# Auxillary_Supply_UCC28740.net
KiCad netlist of a schematic drawn in Altium Designer
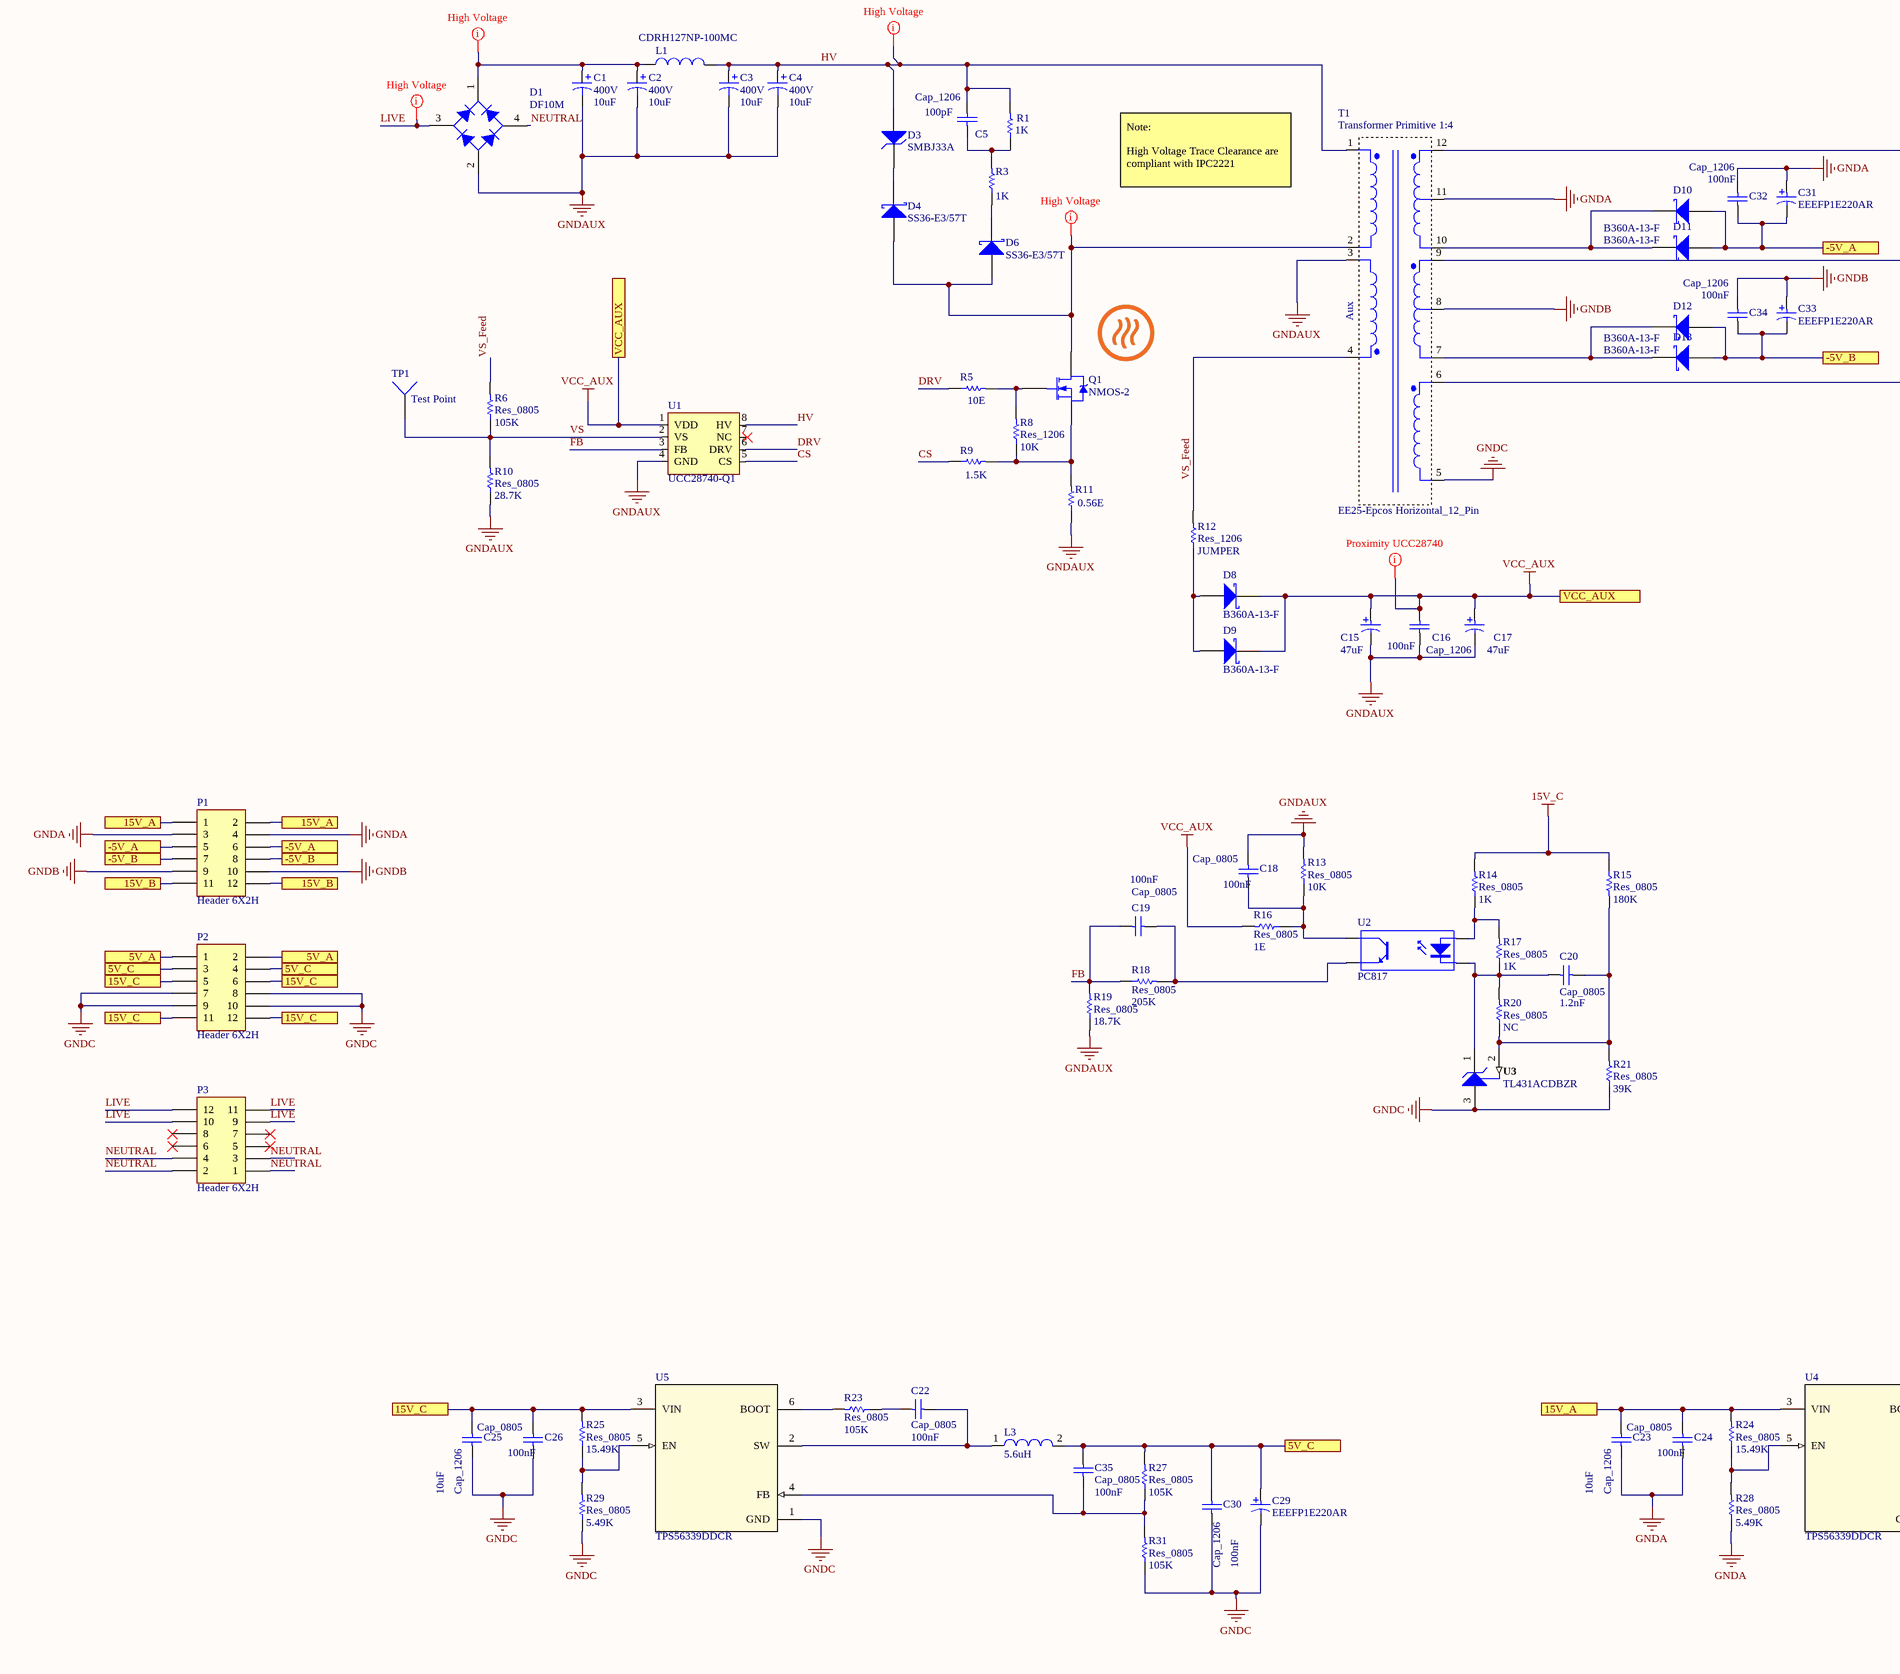
[diagram p0: Auxillary_Supply_UCC28740.SchDoc, left]
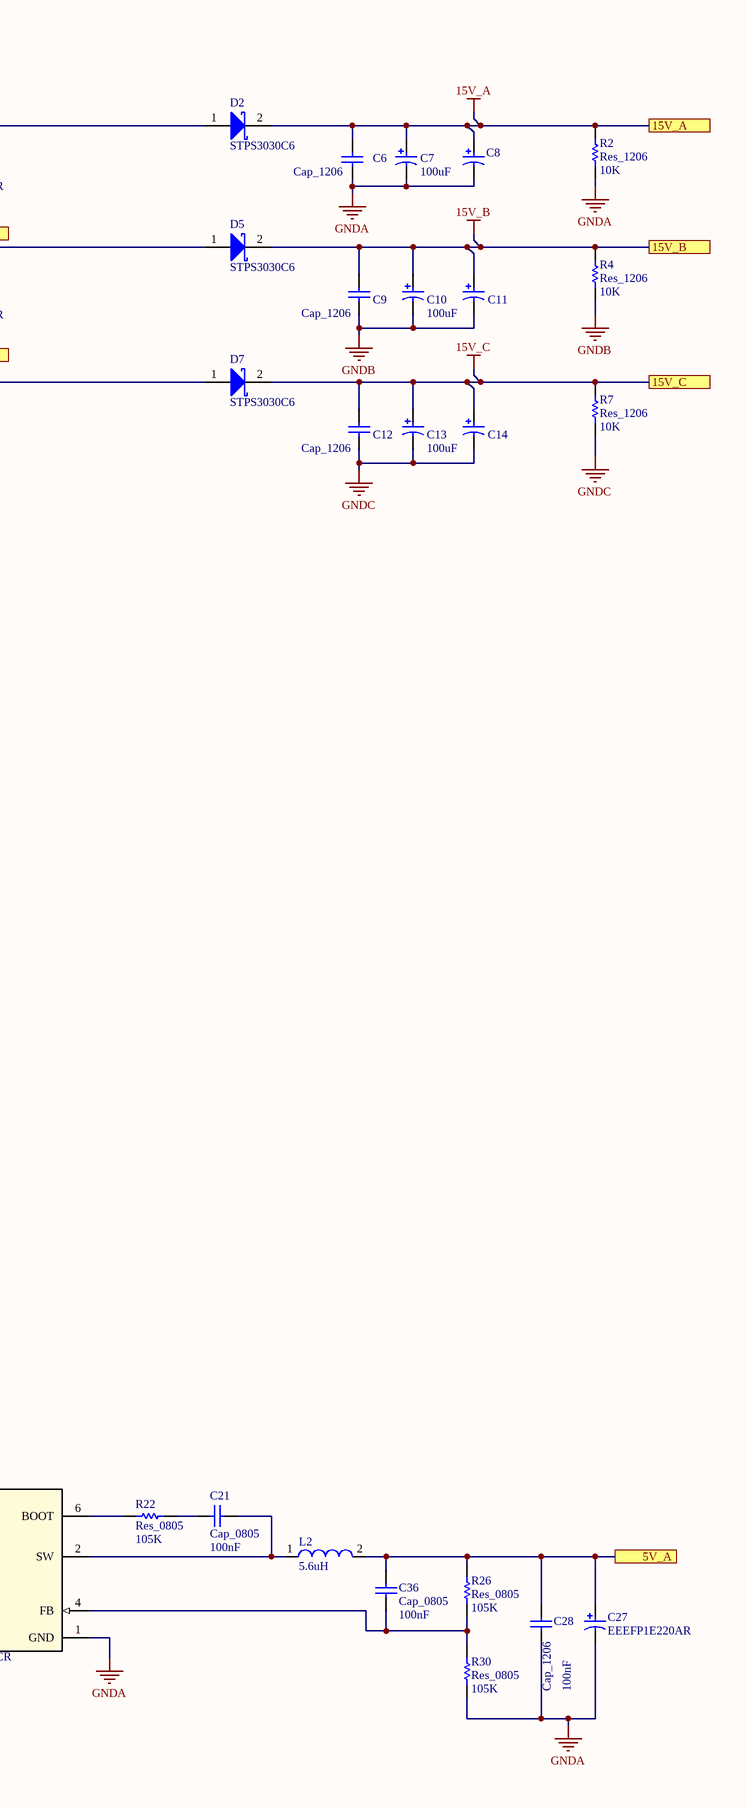
[diagram p1: Auxillary_Supply_UCC28740.SchDoc, right]

(export (version "E")
  (design (tool "Eeschema 10.0.6"))
  (components
    (comp (ref "C1")
      (value "400V")
      (footprint "10uF_400V")
      (description "Polarized Capacitor (Radial)")
      (fields (field (name "ALTIUM_VALUE") "10uF") (field (name "PUBLISHER") "Altium Limited"))
      (libsource (lib "Miscellaneous Devices") (part "Cap Pol1"))
    )
    (comp (ref "C2")
      (value "400V")
      (footprint "10uF_400V")
      (description "Polarized Capacitor (Radial)")
      (fields (field (name "ALTIUM_VALUE") "10uF") (field (name "PUBLISHER") "Altium Limited"))
      (libsource (lib "Miscellaneous Devices") (part "Cap Pol1"))
    )
    (comp (ref "C3")
      (value "400V")
      (footprint "10uF_400V")
      (description "Polarized Capacitor (Radial)")
      (fields (field (name "ALTIUM_VALUE") "10uF") (field (name "PUBLISHER") "Altium Limited"))
      (libsource (lib "Miscellaneous Devices") (part "Cap Pol1"))
    )
    (comp (ref "C4")
      (value "400V")
      (footprint "10uF_400V")
      (description "Polarized Capacitor (Radial)")
      (fields (field (name "ALTIUM_VALUE") "10uF") (field (name "PUBLISHER") "Altium Limited"))
      (libsource (lib "Miscellaneous Devices") (part "Cap Pol1"))
    )
    (comp (ref "C5")
      (value "Cap_1206")
      (footprint "Chip_CAP_1206")
      (description "Capacitor")
      (fields (field (name "ALTIUM_VALUE") "100pF") (field (name "PUBLISHER") "Altium Limited"))
      (libsource (lib "Miscellaneous Devices") (part "Cap"))
    )
    (comp (ref "C6")
      (value "Cap_1206")
      (footprint "Chip_CAP_1206")
      (description "Capacitor")
      (fields (field (name "PUBLISHER") "Altium Limited"))
      (libsource (lib "Miscellaneous Devices") (part "Cap"))
    )
    (comp (ref "C7")
      (value "100uF")
      (footprint "PNSC-FK-V-F_V")
      (fields (field (name "MANUFACTURER") "Panasonic"))
      (libsource (lib "Altium Content Vault") (part "CAP-P-2"))
    )
    (comp (ref "C8")
      (value "100uF")
      (footprint "PNSC-FK-V-F_V")
      (fields (field (name "MANUFACTURER") "Panasonic"))
      (libsource (lib "Altium Content Vault") (part "CAP-P-2"))
    )
    (comp (ref "C9")
      (value "Cap_1206")
      (footprint "Chip_CAP_1206")
      (description "Capacitor")
      (fields (field (name "PUBLISHER") "Altium Limited"))
      (libsource (lib "Miscellaneous Devices") (part "Cap"))
    )
    (comp (ref "C10")
      (value "100uF")
      (footprint "PNSC-FK-V-F_V")
      (fields (field (name "MANUFACTURER") "Panasonic"))
      (libsource (lib "Altium Content Vault") (part "CAP-P-2"))
    )
    (comp (ref "C11")
      (value "100uF")
      (footprint "PNSC-FK-V-F_V")
      (fields (field (name "MANUFACTURER") "Panasonic"))
      (libsource (lib "Altium Content Vault") (part "CAP-P-2"))
    )
    (comp (ref "C12")
      (value "Cap_1206")
      (footprint "Chip_CAP_1206")
      (description "Capacitor")
      (fields (field (name "PUBLISHER") "Altium Limited"))
      (libsource (lib "Miscellaneous Devices") (part "Cap"))
    )
    (comp (ref "C13")
      (value "100uF")
      (footprint "PNSC-FK-V-F_V")
      (fields (field (name "MANUFACTURER") "Panasonic"))
      (libsource (lib "Altium Content Vault") (part "CAP-P-2"))
    )
    (comp (ref "C14")
      (value "100uF")
      (footprint "PNSC-FK-V-F_V")
      (fields (field (name "MANUFACTURER") "Panasonic"))
      (libsource (lib "Altium Content Vault") (part "CAP-P-2"))
    )
    (comp (ref "C15")
      (value "47uF")
      (footprint "PNSC-FP-V-D_V")
      (fields (field (name "MANUFACTURER") "Panasonic"))
      (libsource (lib "Altium Content Vault") (part "CAP-P-2"))
    )
    (comp (ref "C16")
      (value "Cap_1206")
      (footprint "Chip_CAP_1206")
      (description "Capacitor")
      (fields (field (name "ALTIUM_VALUE") "100nF") (field (name "PUBLISHER") "Altium Limited"))
      (libsource (lib "Miscellaneous Devices") (part "Cap"))
    )
    (comp (ref "C17")
      (value "47uF")
      (footprint "PNSC-FP-V-D_V")
      (fields (field (name "MANUFACTURER") "Panasonic"))
      (libsource (lib "Altium Content Vault") (part "CAP-P-2"))
    )
    (comp (ref "C18")
      (value "Cap_0805")
      (footprint "Chip_CAP_0805")
      (description "Capacitor")
      (fields (field (name "SIZE") "100nF") (field (name "PUBLISHER") "Altium Limited"))
      (libsource (lib "Miscellaneous Devices") (part "Cap"))
    )
    (comp (ref "C19")
      (value "Cap_0805")
      (footprint "Chip_CAP_0805")
      (description "Capacitor")
      (fields (field (name "SIZE") "100nF") (field (name "PUBLISHER") "Altium Limited"))
      (libsource (lib "Miscellaneous Devices") (part "Cap"))
    )
    (comp (ref "C20")
      (value "Cap_0805")
      (footprint "Chip_CAP_0805")
      (description "Capacitor")
      (fields (field (name "SIZE") "1.2nF") (field (name "PUBLISHER") "Altium Limited"))
      (libsource (lib "Miscellaneous Devices") (part "Cap"))
    )
    (comp (ref "C21")
      (value "Cap_0805")
      (footprint "Chip_CAP_0805")
      (description "Capacitor")
      (fields (field (name "SIZE") "100nF") (field (name "PUBLISHER") "Altium Limited"))
      (libsource (lib "Miscellaneous Devices") (part "Cap"))
    )
    (comp (ref "C22")
      (value "Cap_0805")
      (footprint "Chip_CAP_0805")
      (description "Capacitor")
      (fields (field (name "SIZE") "100nF") (field (name "PUBLISHER") "Altium Limited"))
      (libsource (lib "Miscellaneous Devices") (part "Cap"))
    )
    (comp (ref "C23")
      (value "Cap_1206")
      (footprint "Chip_CAP_1206")
      (description "Capacitor")
      (fields (field (name "ALTIUM_VALUE") "10uF") (field (name "PUBLISHER") "Altium Limited"))
      (libsource (lib "Miscellaneous Devices") (part "Cap"))
    )
    (comp (ref "C24")
      (value "Cap_0805")
      (footprint "Chip_CAP_0805")
      (description "Capacitor")
      (fields (field (name "SIZE") "100nF") (field (name "PUBLISHER") "Altium Limited"))
      (libsource (lib "Miscellaneous Devices") (part "Cap"))
    )
    (comp (ref "C25")
      (value "Cap_1206")
      (footprint "Chip_CAP_1206")
      (description "Capacitor")
      (fields (field (name "ALTIUM_VALUE") "10uF") (field (name "PUBLISHER") "Altium Limited"))
      (libsource (lib "Miscellaneous Devices") (part "Cap"))
    )
    (comp (ref "C26")
      (value "Cap_0805")
      (footprint "Chip_CAP_0805")
      (description "Capacitor")
      (fields (field (name "SIZE") "100nF") (field (name "PUBLISHER") "Altium Limited"))
      (libsource (lib "Miscellaneous Devices") (part "Cap"))
    )
    (comp (ref "C27")
      (value "EEEFP1E220AR")
      (footprint "PNSC-FP-V-C_V")
      (fields (field (name "MANUFACTURER") "Panasonic"))
      (libsource (lib "Altium Content Vault") (part "CAP-P-2"))
    )
    (comp (ref "C28")
      (value "Cap_1206")
      (footprint "Chip_CAP_1206")
      (description "Capacitor")
      (fields (field (name "ALTIUM_VALUE") "100nF") (field (name "PUBLISHER") "Altium Limited"))
      (libsource (lib "Miscellaneous Devices") (part "Cap"))
    )
    (comp (ref "C29")
      (value "EEEFP1E220AR")
      (footprint "PNSC-FP-V-C_V")
      (fields (field (name "MANUFACTURER") "Panasonic"))
      (libsource (lib "Altium Content Vault") (part "CAP-P-2"))
    )
    (comp (ref "C30")
      (value "Cap_1206")
      (footprint "Chip_CAP_1206")
      (description "Capacitor")
      (fields (field (name "ALTIUM_VALUE") "100nF") (field (name "PUBLISHER") "Altium Limited"))
      (libsource (lib "Miscellaneous Devices") (part "Cap"))
    )
    (comp (ref "C31")
      (value "EEEFP1E220AR")
      (footprint "PNSC-FP-V-C_V")
      (fields (field (name "MANUFACTURER") "Panasonic"))
      (libsource (lib "Altium Content Vault") (part "CAP-P-2"))
    )
    (comp (ref "C32")
      (value "Cap_1206")
      (footprint "Chip_CAP_1206")
      (description "Capacitor")
      (fields (field (name "ALTIUM_VALUE") "100nF") (field (name "PUBLISHER") "Altium Limited"))
      (libsource (lib "Miscellaneous Devices") (part "Cap"))
    )
    (comp (ref "C33")
      (value "EEEFP1E220AR")
      (footprint "PNSC-FP-V-C_V")
      (fields (field (name "MANUFACTURER") "Panasonic"))
      (libsource (lib "Altium Content Vault") (part "CAP-P-2"))
    )
    (comp (ref "C34")
      (value "Cap_1206")
      (footprint "Chip_CAP_1206")
      (description "Capacitor")
      (fields (field (name "ALTIUM_VALUE") "100nF") (field (name "PUBLISHER") "Altium Limited"))
      (libsource (lib "Miscellaneous Devices") (part "Cap"))
    )
    (comp (ref "C35")
      (value "Cap_0805")
      (footprint "Chip_CAP_0805")
      (description "Capacitor")
      (fields (field (name "SIZE") "100nF") (field (name "PUBLISHER") "Altium Limited"))
      (libsource (lib "Miscellaneous Devices") (part "Cap"))
    )
    (comp (ref "C36")
      (value "Cap_0805")
      (footprint "Chip_CAP_0805")
      (description "Capacitor")
      (fields (field (name "SIZE") "100nF") (field (name "PUBLISHER") "Altium Limited"))
      (libsource (lib "Miscellaneous Devices") (part "Cap"))
    )
    (comp (ref "D1")
      (value "DF10M")
      (footprint "DF10M")
      (libsource (lib "Auxillary_Supply_UCC28740") (part "DF10M"))
    )
    (comp (ref "D2")
      (value "STPS3030C6")
      (footprint "DPAK254P1542X450-4N")
      (description "Schottky Rectifier")
      (fields (field (name "PUBLISHER") "Altium Limited"))
      (libsource (lib "IR Rectifier - Schottky") (part "11DQ06"))
    )
    (comp (ref "D3")
      (value "SMBJ33A")
      (footprint "FAIR-DO-214AA-2_V")
      (description "Transient Voltage Suppressor, 600 W, 33 V, -55 to 150 degC, 2-Pin SMD, RoHS, Tape and Reel")
      (fields (field (name "MANUFACTURER") "FairchildSemiconductor"))
      (libsource (lib "Altium Content Vault") (part "DZEN-AK-2"))
    )
    (comp (ref "D4")
      (value "SS36-E3/57T")
      (footprint "VISH-DO-214AB-2_V")
      (fields (field (name "MANUFACTURER") "Vishay"))
      (libsource (lib "Altium Content Vault") (part "DSKY-AK-2"))
    )
    (comp (ref "D5")
      (value "STPS3030C6")
      (footprint "DPAK254P1542X450-4N")
      (description "Schottky Rectifier")
      (fields (field (name "PUBLISHER") "Altium Limited"))
      (libsource (lib "IR Rectifier - Schottky") (part "11DQ06"))
    )
    (comp (ref "D6")
      (value "SS36-E3/57T")
      (footprint "VISH-DO-214AB-2_V")
      (fields (field (name "MANUFACTURER") "Vishay"))
      (libsource (lib "Altium Content Vault") (part "DSKY-AK-2"))
    )
    (comp (ref "D7")
      (value "STPS3030C6")
      (footprint "DPAK254P1542X450-4N")
      (description "Schottky Rectifier")
      (fields (field (name "PUBLISHER") "Altium Limited"))
      (libsource (lib "IR Rectifier - Schottky") (part "11DQ06"))
    )
    (comp (ref "D8")
      (value "B360A-13-F")
      (footprint "DIOD-B360A_V")
      (description "Schottky Barrier Rectifier, 3 A, -55 to 150 degC, 2-Pin Molded, RoHS, Tape and Reel")
      (fields (field (name "MANUFACTURER") "DiodesIncorporated"))
      (libsource (lib "Altium Content Vault") (part "DSKY-AK-2"))
    )
    (comp (ref "D9")
      (value "B360A-13-F")
      (footprint "DIOD-B360A_V")
      (description "Schottky Barrier Rectifier, 3 A, -55 to 150 degC, 2-Pin Molded, RoHS, Tape and Reel")
      (fields (field (name "MANUFACTURER") "DiodesIncorporated"))
      (libsource (lib "Altium Content Vault") (part "DSKY-AK-2"))
    )
    (comp (ref "D10")
      (value "B360A-13-F")
      (footprint "DIOD-B360A_V")
      (description "Schottky Barrier Rectifier, 3 A, -55 to 150 degC, 2-Pin Molded, RoHS, Tape and Reel")
      (fields (field (name "MANUFACTURER") "DiodesIncorporated"))
      (libsource (lib "Altium Content Vault") (part "DSKY-AK-2"))
    )
    (comp (ref "D11")
      (value "B360A-13-F")
      (footprint "DIOD-B360A_V")
      (description "Schottky Barrier Rectifier, 3 A, -55 to 150 degC, 2-Pin Molded, RoHS, Tape and Reel")
      (fields (field (name "MANUFACTURER") "DiodesIncorporated"))
      (libsource (lib "Altium Content Vault") (part "DSKY-AK-2"))
    )
    (comp (ref "D12")
      (value "B360A-13-F")
      (footprint "DIOD-B360A_V")
      (description "Schottky Barrier Rectifier, 3 A, -55 to 150 degC, 2-Pin Molded, RoHS, Tape and Reel")
      (fields (field (name "MANUFACTURER") "DiodesIncorporated"))
      (libsource (lib "Altium Content Vault") (part "DSKY-AK-2"))
    )
    (comp (ref "D13")
      (value "B360A-13-F")
      (footprint "DIOD-B360A_V")
      (description "Schottky Barrier Rectifier, 3 A, -55 to 150 degC, 2-Pin Molded, RoHS, Tape and Reel")
      (fields (field (name "MANUFACTURER") "DiodesIncorporated"))
      (libsource (lib "Altium Content Vault") (part "DSKY-AK-2"))
    )
    (comp (ref "L1")
      (value "CDRH127NP-100MC")
      (footprint "SUMI-CDRH127_V")
      (description "Power Inductor, 10 uH, +/- 20%, -40 to 100 degC, 2-Pin SMD, RoHS, Tape and Reel")
      (fields (field (name "MANUFACTURER") "Sumida") (field (name "TOLERANCE") "±20%"))
      (libsource (lib "Altium Content Vault") (part "IND-2"))
    )
    (comp (ref "L2")
      (value "5.6uH")
      (footprint "WE-PD-L")
      (description "SMD-Shielded Power Inductor WE-PD, L = 4.70 µH")
      (libsource (lib "Altium Content Vault") (part "PAS-IND-INDUCTOR-2"))
    )
    (comp (ref "L3")
      (value "5.6uH")
      (footprint "WE-PD-L")
      (description "SMD-Shielded Power Inductor WE-PD, L = 4.70 µH")
      (libsource (lib "Altium Content Vault") (part "PAS-IND-INDUCTOR-2"))
    )
    (comp (ref "P1")
      (value "Header 6X2H")
      (footprint "Header_6X2")
      (description "Header, 6-Pin, Dual row, Right Angle")
      (fields (field (name "PUBLISHER") "Altium Limited"))
      (libsource (lib "Miscellaneous Connectors") (part "Header 6X2H"))
    )
    (comp (ref "P2")
      (value "Header 6X2H")
      (footprint "Header_6X2")
      (description "Header, 6-Pin, Dual row, Right Angle")
      (fields (field (name "PUBLISHER") "Altium Limited"))
      (libsource (lib "Miscellaneous Connectors") (part "Header 6X2H"))
    )
    (comp (ref "P3")
      (value "Header 6X2H")
      (footprint "Header_6X2")
      (description "Header, 6-Pin, Dual row, Right Angle")
      (fields (field (name "PUBLISHER") "Altium Limited"))
      (libsource (lib "") (part "Header 6X2H_1"))
    )
    (comp (ref "Q1")
      (value "NMOS-2")
      (footprint "DPAK254P1542X450-3N - Thermal")
      (description "N-Channel Power MOSFET")
      (fields (field (name "PUBLISHER") "Altium Limited"))
      (libsource (lib "Miscellaneous Devices") (part "NMOS-2"))
    )
    (comp (ref "R1")
      (value "1K")
      (footprint "Chip_Res_1206")
      (description "Resistor")
      (fields (field (name "Comment") "Res_1206") (field (name "PUBLISHER") "Altium Limited"))
      (libsource (lib "Miscellaneous Devices") (part "Res1"))
    )
    (comp (ref "R2")
      (value "Res_1206")
      (footprint "Chip_Res_1206")
      (description "Resistor")
      (fields (field (name "ALTIUM_VALUE") "10K") (field (name "PUBLISHER") "Altium Limited"))
      (libsource (lib "Miscellaneous Devices") (part "Res1"))
    )
    (comp (ref "R3")
      (value "1K")
      (footprint "Chip_Res_1206")
      (description "Resistor")
      (fields (field (name "Comment") "Res_1206") (field (name "PUBLISHER") "Altium Limited"))
      (libsource (lib "Miscellaneous Devices") (part "Res1"))
    )
    (comp (ref "R4")
      (value "Res_1206")
      (footprint "Chip_Res_1206")
      (description "Resistor")
      (fields (field (name "ALTIUM_VALUE") "10K") (field (name "PUBLISHER") "Altium Limited"))
      (libsource (lib "Miscellaneous Devices") (part "Res1"))
    )
    (comp (ref "R5")
      (value "10E")
      (footprint "Chip_Res_1206")
      (description "Resistor")
      (fields (field (name "Comment") "Res_1206") (field (name "PUBLISHER") "Altium Limited"))
      (libsource (lib "Miscellaneous Devices") (part "Res1"))
    )
    (comp (ref "R6")
      (value "Res_0805")
      (footprint "Chip_Res_0805")
      (description "Resistor")
      (fields (field (name "ALTIUM_VALUE") "105K") (field (name "PUBLISHER") "Altium Limited"))
      (libsource (lib "Miscellaneous Devices") (part "Res1"))
    )
    (comp (ref "R7")
      (value "Res_1206")
      (footprint "Chip_Res_1206")
      (description "Resistor")
      (fields (field (name "ALTIUM_VALUE") "10K") (field (name "PUBLISHER") "Altium Limited"))
      (libsource (lib "Miscellaneous Devices") (part "Res1"))
    )
    (comp (ref "R8")
      (value "Res_1206")
      (footprint "Chip_Res_1206")
      (description "Resistor")
      (fields (field (name "ALTIUM_VALUE") "10K") (field (name "PUBLISHER") "Altium Limited"))
      (libsource (lib "Miscellaneous Devices") (part "Res1"))
    )
    (comp (ref "R9")
      (value "1.5K")
      (footprint "Chip_Res_1206")
      (description "Resistor")
      (fields (field (name "Comment") "Res_1206") (field (name "PUBLISHER") "Altium Limited"))
      (libsource (lib "Miscellaneous Devices") (part "Res1"))
    )
    (comp (ref "R10")
      (value "Res_0805")
      (footprint "Chip_Res_0805")
      (description "Resistor")
      (fields (field (name "ALTIUM_VALUE") "28.7K") (field (name "PUBLISHER") "Altium Limited"))
      (libsource (lib "Miscellaneous Devices") (part "Res1"))
    )
    (comp (ref "R11")
      (value "0.56E")
      (footprint "Chip2PinSM127P600-8N_2512")
      (description "Resistor")
      (fields (field (name "Comment") "Res_2512") (field (name "PUBLISHER") "Altium Limited"))
      (libsource (lib "Miscellaneous Devices") (part "Res1"))
    )
    (comp (ref "R12")
      (value "Res_1206")
      (footprint "Chip_Res_1206")
      (description "Resistor")
      (fields (field (name "ALTIUM_VALUE") "JUMPER") (field (name "PUBLISHER") "Altium Limited"))
      (libsource (lib "Miscellaneous Devices") (part "Res1"))
    )
    (comp (ref "R13")
      (value "Res_0805")
      (footprint "Chip_Res_0805")
      (description "Resistor")
      (fields (field (name "ALTIUM_VALUE") "10K") (field (name "PUBLISHER") "Altium Limited"))
      (libsource (lib "Miscellaneous Devices") (part "Res1"))
    )
    (comp (ref "R14")
      (value "Res_0805")
      (footprint "Chip_Res_0805")
      (description "Resistor")
      (fields (field (name "ALTIUM_VALUE") "1K") (field (name "PUBLISHER") "Altium Limited"))
      (libsource (lib "Miscellaneous Devices") (part "Res1"))
    )
    (comp (ref "R15")
      (value "Res_0805")
      (footprint "Chip_Res_0805")
      (description "Resistor")
      (fields (field (name "ALTIUM_VALUE") "180K") (field (name "PUBLISHER") "Altium Limited"))
      (libsource (lib "Miscellaneous Devices") (part "Res1"))
    )
    (comp (ref "R16")
      (value "Res_0805")
      (footprint "Chip_Res_0805")
      (description "Resistor")
      (fields (field (name "ALTIUM_VALUE") "1E") (field (name "PUBLISHER") "Altium Limited"))
      (libsource (lib "Miscellaneous Devices") (part "Res1"))
    )
    (comp (ref "R17")
      (value "Res_0805")
      (footprint "Chip_Res_0805")
      (description "Resistor")
      (fields (field (name "ALTIUM_VALUE") "1K") (field (name "PUBLISHER") "Altium Limited"))
      (libsource (lib "Miscellaneous Devices") (part "Res1"))
    )
    (comp (ref "R18")
      (value "Res_0805")
      (footprint "Chip_Res_0805")
      (description "Resistor")
      (fields (field (name "ALTIUM_VALUE") "205K") (field (name "PUBLISHER") "Altium Limited"))
      (libsource (lib "Miscellaneous Devices") (part "Res1"))
    )
    (comp (ref "R19")
      (value "Res_0805")
      (footprint "Chip_Res_0805")
      (description "Resistor")
      (fields (field (name "ALTIUM_VALUE") "18.7K") (field (name "PUBLISHER") "Altium Limited"))
      (libsource (lib "Miscellaneous Devices") (part "Res1"))
    )
    (comp (ref "R20")
      (value "Res_0805")
      (footprint "Chip_Res_0805")
      (description "Resistor")
      (fields (field (name "ALTIUM_VALUE") "NC") (field (name "PUBLISHER") "Altium Limited"))
      (libsource (lib "Miscellaneous Devices") (part "Res1"))
    )
    (comp (ref "R21")
      (value "Res_0805")
      (footprint "Chip_Res_0805")
      (description "Resistor")
      (fields (field (name "ALTIUM_VALUE") "39K") (field (name "PUBLISHER") "Altium Limited"))
      (libsource (lib "Miscellaneous Devices") (part "Res1"))
    )
    (comp (ref "R22")
      (value "Res_0805")
      (footprint "Chip_Res_0805")
      (description "Resistor")
      (fields (field (name "ALTIUM_VALUE") "105K") (field (name "PUBLISHER") "Altium Limited"))
      (libsource (lib "Miscellaneous Devices") (part "Res1"))
    )
    (comp (ref "R23")
      (value "Res_0805")
      (footprint "Chip_Res_0805")
      (description "Resistor")
      (fields (field (name "ALTIUM_VALUE") "105K") (field (name "PUBLISHER") "Altium Limited"))
      (libsource (lib "Miscellaneous Devices") (part "Res1"))
    )
    (comp (ref "R24")
      (value "Res_0805")
      (footprint "Chip_Res_0805")
      (description "Resistor")
      (fields (field (name "ALTIUM_VALUE") "15.49K") (field (name "PUBLISHER") "Altium Limited"))
      (libsource (lib "Miscellaneous Devices") (part "Res1"))
    )
    (comp (ref "R25")
      (value "Res_0805")
      (footprint "Chip_Res_0805")
      (description "Resistor")
      (fields (field (name "ALTIUM_VALUE") "15.49K") (field (name "PUBLISHER") "Altium Limited"))
      (libsource (lib "Miscellaneous Devices") (part "Res1"))
    )
    (comp (ref "R26")
      (value "Res_0805")
      (footprint "Chip_Res_0805")
      (description "Resistor")
      (fields (field (name "ALTIUM_VALUE") "105K") (field (name "PUBLISHER") "Altium Limited"))
      (libsource (lib "Miscellaneous Devices") (part "Res1"))
    )
    (comp (ref "R27")
      (value "Res_0805")
      (footprint "Chip_Res_0805")
      (description "Resistor")
      (fields (field (name "ALTIUM_VALUE") "105K") (field (name "PUBLISHER") "Altium Limited"))
      (libsource (lib "Miscellaneous Devices") (part "Res1"))
    )
    (comp (ref "R28")
      (value "Res_0805")
      (footprint "Chip_Res_0805")
      (description "Resistor")
      (fields (field (name "ALTIUM_VALUE") "5.49K") (field (name "PUBLISHER") "Altium Limited"))
      (libsource (lib "Miscellaneous Devices") (part "Res1"))
    )
    (comp (ref "R29")
      (value "Res_0805")
      (footprint "Chip_Res_0805")
      (description "Resistor")
      (fields (field (name "ALTIUM_VALUE") "5.49K") (field (name "PUBLISHER") "Altium Limited"))
      (libsource (lib "Miscellaneous Devices") (part "Res1"))
    )
    (comp (ref "R30")
      (value "Res_0805")
      (footprint "Chip_Res_0805")
      (description "Resistor")
      (fields (field (name "ALTIUM_VALUE") "105K") (field (name "PUBLISHER") "Altium Limited"))
      (libsource (lib "Miscellaneous Devices") (part "Res1"))
    )
    (comp (ref "R31")
      (value "Res_0805")
      (footprint "Chip_Res_0805")
      (description "Resistor")
      (fields (field (name "ALTIUM_VALUE") "105K") (field (name "PUBLISHER") "Altium Limited"))
      (libsource (lib "Miscellaneous Devices") (part "Res1"))
    )
    (comp (ref "T1")
      (value "EE25-Epcos Horizontal_12_Pin")
      (footprint "PQ26_20")
      (libsource (lib "Auxillary_Supply_UCC28740") (part "EE25-Epcos Horizontal_12_Pin"))
    )
    (comp (ref "TP1")
      (value "Test Point")
      (footprint "PIN1")
      (fields (field (name "PUBLISHER") "Altium Limited"))
      (libsource (lib "Miscellaneous Connectors") (part "Socket"))
    )
    (comp (ref "U1")
      (value "UCC28740-Q1")
      (footprint "SOIC127P570X175_HS-9N")
      (libsource (lib "Auxillary_Supply_UCC28740") (part "UCC28740-Q1"))
    )
    (comp (ref "U2")
      (value "PC817")
      (footprint "LTV-817")
      (description "4-Pin Phototransistor Optocoupler")
      (fields (field (name "PUBLISHER") "Altium Limited"))
      (libsource (lib "Miscellaneous Devices") (part "Optoisolator1"))
    )
    (comp (ref "U3")
      (value "TL431ACDBZR")
      (footprint "DBZ0003A_L")
      (fields (field (name "MANUFACTURER") "Texas Instruments"))
      (libsource (lib "Altium Content Vault") (part "TI-TL431ADBZ3"))
    )
    (comp (ref "U4")
      (value "TPS56339DDCR")
      (footprint "SOT95P278X110-6N")
      (description "Imported")
      (fields (field (name "MANUFACTURER") "Texas Instruments"))
      (libsource (lib "Auxillary_Supply_UCC28740") (part "TPS56339DDCR"))
    )
    (comp (ref "U5")
      (value "TPS56339DDCR")
      (footprint "SOT95P278X110-6N")
      (description "Imported")
      (fields (field (name "MANUFACTURER") "Texas Instruments"))
      (libsource (lib "Auxillary_Supply_UCC28740") (part "TPS56339DDCR"))
    )
  )
  (nets
    (net (code "1") (name "/-5V_A") (class "Default")
      (node (ref "C31") (pin "2") (pinfunction "2_2") (pintype "passive"))
      (node (ref "C32") (pin "2") (pinfunction "2_2") (pintype "passive"))
      (node (ref "D10") (pin "1") (pinfunction "A_1") (pintype "passive"))
      (node (ref "D11") (pin "1") (pinfunction "A_1") (pintype "passive"))
      (node (ref "P1") (pin "5") (pinfunction "5_5") (pintype "passive"))
      (node (ref "P1") (pin "6") (pinfunction "6_6") (pintype "passive"))
    )
    (net (code "2") (name "/-5V_B") (class "Default")
      (node (ref "C33") (pin "2") (pinfunction "2_2") (pintype "passive"))
      (node (ref "C34") (pin "2") (pinfunction "2_2") (pintype "passive"))
      (node (ref "D12") (pin "1") (pinfunction "A_1") (pintype "passive"))
      (node (ref "D13") (pin "1") (pinfunction "A_1") (pintype "passive"))
      (node (ref "P1") (pin "7") (pinfunction "7_7") (pintype "passive"))
      (node (ref "P1") (pin "8") (pinfunction "8_8") (pintype "passive"))
    )
    (net (code "3") (name "/5V_A") (class "Default")
      (node (ref "C27") (pin "1") (pinfunction "1_1") (pintype "passive"))
      (node (ref "C28") (pin "1") (pinfunction "1_1") (pintype "passive"))
      (node (ref "C36") (pin "2") (pinfunction "2_2") (pintype "passive"))
      (node (ref "L2") (pin "2") (pinfunction "2_2") (pintype "passive"))
      (node (ref "P2") (pin "1") (pinfunction "1_1") (pintype "passive"))
      (node (ref "P2") (pin "2") (pinfunction "2_2") (pintype "passive"))
      (node (ref "R26") (pin "2") (pinfunction "2_2") (pintype "passive"))
    )
    (net (code "4") (name "/5V_C") (class "Default")
      (node (ref "C29") (pin "1") (pinfunction "1_1") (pintype "passive"))
      (node (ref "C30") (pin "1") (pinfunction "1_1") (pintype "passive"))
      (node (ref "C35") (pin "2") (pinfunction "2_2") (pintype "passive"))
      (node (ref "L3") (pin "2") (pinfunction "2_2") (pintype "passive"))
      (node (ref "P2") (pin "3") (pinfunction "3_3") (pintype "passive"))
      (node (ref "P2") (pin "4") (pinfunction "4_4") (pintype "passive"))
      (node (ref "R27") (pin "2") (pinfunction "2_2") (pintype "passive"))
    )
    (net (code "6") (name "/CS") (class "Default")
      (node (ref "R9") (pin "1") (pinfunction "1_1") (pintype "passive"))
      (node (ref "U1") (pin "5") (pinfunction "CS_5") (pintype "passive"))
    )
    (net (code "7") (name "/DRV") (class "Default")
      (node (ref "R5") (pin "1") (pinfunction "1_1") (pintype "passive"))
      (node (ref "U1") (pin "6") (pinfunction "DRV_6") (pintype "passive"))
    )
    (net (code "8") (name "/FB") (class "Default")
      (node (ref "C19") (pin "2") (pinfunction "2_2") (pintype "passive"))
      (node (ref "R18") (pin "1") (pinfunction "1_1") (pintype "passive"))
      (node (ref "R19") (pin "2") (pinfunction "2_2") (pintype "passive"))
      (node (ref "U1") (pin "3") (pinfunction "FB_3") (pintype "passive"))
    )
    (net (code "9") (name "/HV") (class "Default")
      (node (ref "C3") (pin "1") (pinfunction "1_1") (pintype "passive"))
      (node (ref "C4") (pin "1") (pinfunction "1_1") (pintype "passive"))
      (node (ref "C5") (pin "2") (pinfunction "2_2") (pintype "passive"))
      (node (ref "D3") (pin "1") (pinfunction "A_1") (pintype "passive"))
      (node (ref "L1") (pin "2") (pinfunction "2_2") (pintype "passive"))
      (node (ref "R1") (pin "2") (pinfunction "2_2") (pintype "passive"))
      (node (ref "T1") (pin "1") (pinfunction "1_1") (pintype "passive"))
      (node (ref "U1") (pin "8") (pinfunction "HV_8") (pintype "passive"))
    )
    (net (code "10") (name "/LIVE") (class "Default")
      (node (ref "D1") (pin "3") (pinfunction "C_3") (pintype "passive"))
      (node (ref "P3") (pin "10") (pinfunction "10_10") (pintype "passive"))
      (node (ref "P3") (pin "11") (pinfunction "11_11") (pintype "passive"))
      (node (ref "P3") (pin "12") (pinfunction "12_12") (pintype "passive"))
      (node (ref "P3") (pin "9") (pinfunction "9_9") (pintype "passive"))
    )
    (net (code "11") (name "/NEUTRAL") (class "Default")
      (node (ref "D1") (pin "4") (pinfunction "C_4") (pintype "passive"))
      (node (ref "P3") (pin "1") (pinfunction "1_1") (pintype "passive"))
      (node (ref "P3") (pin "2") (pinfunction "2_2") (pintype "passive"))
      (node (ref "P3") (pin "3") (pinfunction "3_3") (pintype "passive"))
      (node (ref "P3") (pin "4") (pinfunction "4_4") (pintype "passive"))
    )
    (net (code "12") (name "/VS") (class "Default")
      (node (ref "R10") (pin "2") (pinfunction "2_2") (pintype "passive"))
      (node (ref "R6") (pin "1") (pinfunction "1_1") (pintype "passive"))
      (node (ref "TP1") (pin "1") (pinfunction "1_1") (pintype "passive"))
      (node (ref "U1") (pin "2") (pinfunction "VS_2") (pintype "passive"))
    )
    (net (code "13") (name "/VS_Feed") (class "Default")
      (node (ref "R12") (pin "2") (pinfunction "2_2") (pintype "passive"))
      (node (ref "R6") (pin "2") (pinfunction "2_2") (pintype "passive"))
      (node (ref "T1") (pin "4") (pinfunction "4_4") (pintype "passive"))
    )
    (net (code "14") (name "15V_A") (class "Default")
      (node (ref "C23") (pin "1") (pinfunction "1_1") (pintype "passive"))
      (node (ref "C24") (pin "1") (pinfunction "1_1") (pintype "passive"))
      (node (ref "C6") (pin "2") (pinfunction "2_2") (pintype "passive"))
      (node (ref "C7") (pin "1") (pinfunction "1_1") (pintype "passive"))
      (node (ref "C8") (pin "1") (pinfunction "1_1") (pintype "passive"))
      (node (ref "D2") (pin "2") (pinfunction "K_2") (pintype "passive"))
      (node (ref "P1") (pin "1") (pinfunction "1_1") (pintype "passive"))
      (node (ref "P1") (pin "2") (pinfunction "2_2") (pintype "passive"))
      (node (ref "R2") (pin "2") (pinfunction "2_2") (pintype "passive"))
      (node (ref "R24") (pin "2") (pinfunction "2_2") (pintype "passive"))
      (node (ref "U4") (pin "3") (pinfunction "VIN_3") (pintype "power_in"))
    )
    (net (code "15") (name "15V_B") (class "Default")
      (node (ref "C10") (pin "1") (pinfunction "1_1") (pintype "passive"))
      (node (ref "C11") (pin "1") (pinfunction "1_1") (pintype "passive"))
      (node (ref "C9") (pin "2") (pinfunction "2_2") (pintype "passive"))
      (node (ref "D5") (pin "2") (pinfunction "K_2") (pintype "passive"))
      (node (ref "P1") (pin "11") (pinfunction "11_11") (pintype "passive"))
      (node (ref "P1") (pin "12") (pinfunction "12_12") (pintype "passive"))
      (node (ref "R4") (pin "2") (pinfunction "2_2") (pintype "passive"))
    )
    (net (code "16") (name "15V_C") (class "Default")
      (node (ref "C12") (pin "2") (pinfunction "2_2") (pintype "passive"))
      (node (ref "C13") (pin "1") (pinfunction "1_1") (pintype "passive"))
      (node (ref "C14") (pin "1") (pinfunction "1_1") (pintype "passive"))
      (node (ref "C25") (pin "1") (pinfunction "1_1") (pintype "passive"))
      (node (ref "C26") (pin "1") (pinfunction "1_1") (pintype "passive"))
      (node (ref "D7") (pin "2") (pinfunction "K_2") (pintype "passive"))
      (node (ref "P2") (pin "11") (pinfunction "11_11") (pintype "passive"))
      (node (ref "P2") (pin "12") (pinfunction "12_12") (pintype "passive"))
      (node (ref "P2") (pin "5") (pinfunction "5_5") (pintype "passive"))
      (node (ref "P2") (pin "6") (pinfunction "6_6") (pintype "passive"))
      (node (ref "R14") (pin "2") (pinfunction "2_2") (pintype "passive"))
      (node (ref "R15") (pin "1") (pinfunction "1_1") (pintype "passive"))
      (node (ref "R25") (pin "2") (pinfunction "2_2") (pintype "passive"))
      (node (ref "R7") (pin "2") (pinfunction "2_2") (pintype "passive"))
      (node (ref "U5") (pin "3") (pinfunction "VIN_3") (pintype "power_in"))
    )
    (net (code "17") (name "GNDA") (class "Default")
      (node (ref "C23") (pin "2") (pinfunction "2_2") (pintype "passive"))
      (node (ref "C24") (pin "2") (pinfunction "2_2") (pintype "passive"))
      (node (ref "C27") (pin "2") (pinfunction "2_2") (pintype "passive"))
      (node (ref "C28") (pin "2") (pinfunction "2_2") (pintype "passive"))
      (node (ref "C31") (pin "1") (pinfunction "1_1") (pintype "passive"))
      (node (ref "C32") (pin "1") (pinfunction "1_1") (pintype "passive"))
      (node (ref "C6") (pin "1") (pinfunction "1_1") (pintype "passive"))
      (node (ref "C7") (pin "2") (pinfunction "2_2") (pintype "passive"))
      (node (ref "C8") (pin "2") (pinfunction "2_2") (pintype "passive"))
      (node (ref "P1") (pin "3") (pinfunction "3_3") (pintype "passive"))
      (node (ref "P1") (pin "4") (pinfunction "4_4") (pintype "passive"))
      (node (ref "R2") (pin "1") (pinfunction "1_1") (pintype "passive"))
      (node (ref "R28") (pin "1") (pinfunction "1_1") (pintype "passive"))
      (node (ref "R30") (pin "1") (pinfunction "1_1") (pintype "passive"))
      (node (ref "T1") (pin "11") (pinfunction "11_11") (pintype "passive"))
      (node (ref "U4") (pin "1") (pinfunction "GND_1") (pintype "power_in"))
    )
    (net (code "18") (name "GNDAUX") (class "Default")
      (node (ref "C1") (pin "2") (pinfunction "2_2") (pintype "passive"))
      (node (ref "C15") (pin "2") (pinfunction "2_2") (pintype "passive"))
      (node (ref "C16") (pin "1") (pinfunction "1_1") (pintype "passive"))
      (node (ref "C17") (pin "2") (pinfunction "2_2") (pintype "passive"))
      (node (ref "C18") (pin "1") (pinfunction "1_1") (pintype "passive"))
      (node (ref "C2") (pin "2") (pinfunction "2_2") (pintype "passive"))
      (node (ref "C3") (pin "2") (pinfunction "2_2") (pintype "passive"))
      (node (ref "C4") (pin "2") (pinfunction "2_2") (pintype "passive"))
      (node (ref "D1") (pin "2") (pinfunction "A_2") (pintype "passive"))
      (node (ref "R10") (pin "1") (pinfunction "1_1") (pintype "passive"))
      (node (ref "R11") (pin "1") (pinfunction "1_1") (pintype "passive"))
      (node (ref "R13") (pin "2") (pinfunction "2_2") (pintype "passive"))
      (node (ref "R19") (pin "1") (pinfunction "1_1") (pintype "passive"))
      (node (ref "T1") (pin "3") (pinfunction "3_3") (pintype "passive"))
      (node (ref "U1") (pin "4") (pinfunction "GND_4") (pintype "power_in"))
    )
    (net (code "19") (name "GNDB") (class "Default")
      (node (ref "C10") (pin "2") (pinfunction "2_2") (pintype "passive"))
      (node (ref "C11") (pin "2") (pinfunction "2_2") (pintype "passive"))
      (node (ref "C33") (pin "1") (pinfunction "1_1") (pintype "passive"))
      (node (ref "C34") (pin "1") (pinfunction "1_1") (pintype "passive"))
      (node (ref "C9") (pin "1") (pinfunction "1_1") (pintype "passive"))
      (node (ref "P1") (pin "10") (pinfunction "10_10") (pintype "passive"))
      (node (ref "P1") (pin "9") (pinfunction "9_9") (pintype "passive"))
      (node (ref "R4") (pin "1") (pinfunction "1_1") (pintype "passive"))
      (node (ref "T1") (pin "8") (pinfunction "8_8") (pintype "passive"))
    )
    (net (code "20") (name "GNDC") (class "Default")
      (node (ref "C12") (pin "1") (pinfunction "1_1") (pintype "passive"))
      (node (ref "C13") (pin "2") (pinfunction "2_2") (pintype "passive"))
      (node (ref "C14") (pin "2") (pinfunction "2_2") (pintype "passive"))
      (node (ref "C25") (pin "2") (pinfunction "2_2") (pintype "passive"))
      (node (ref "C26") (pin "2") (pinfunction "2_2") (pintype "passive"))
      (node (ref "C29") (pin "2") (pinfunction "2_2") (pintype "passive"))
      (node (ref "C30") (pin "2") (pinfunction "2_2") (pintype "passive"))
      (node (ref "P2") (pin "10") (pinfunction "10_10") (pintype "passive"))
      (node (ref "P2") (pin "7") (pinfunction "7_7") (pintype "passive"))
      (node (ref "P2") (pin "8") (pinfunction "8_8") (pintype "passive"))
      (node (ref "P2") (pin "9") (pinfunction "9_9") (pintype "passive"))
      (node (ref "R21") (pin "1") (pinfunction "1_1") (pintype "passive"))
      (node (ref "R29") (pin "1") (pinfunction "1_1") (pintype "passive"))
      (node (ref "R31") (pin "1") (pinfunction "1_1") (pintype "passive"))
      (node (ref "R7") (pin "1") (pinfunction "1_1") (pintype "passive"))
      (node (ref "T1") (pin "5") (pinfunction "5_5") (pintype "passive"))
      (node (ref "U3") (pin "3") (pinfunction "ANODE_3") (pintype "passive"))
      (node (ref "U5") (pin "1") (pinfunction "GND_1") (pintype "power_in"))
    )
    (net (code "21") (name "Net-(C5-Pad1)") (class "Default")
      (node (ref "C5") (pin "1") (pinfunction "1_1") (pintype "passive"))
      (node (ref "R1") (pin "1") (pinfunction "1_1") (pintype "passive"))
      (node (ref "R3") (pin "2") (pinfunction "2_2") (pintype "passive"))
    )
    (net (code "22") (name "Net-(C21-Pad1)") (class "Default")
      (node (ref "C21") (pin "1") (pinfunction "1_1") (pintype "passive"))
      (node (ref "R22") (pin "1") (pinfunction "1_1") (pintype "passive"))
    )
    (net (code "23") (name "Net-(C22-Pad1)") (class "Default")
      (node (ref "C22") (pin "1") (pinfunction "1_1") (pintype "passive"))
      (node (ref "R23") (pin "1") (pinfunction "1_1") (pintype "passive"))
    )
    (net (code "24") (name "Net-(D1-K)") (class "Default")
      (node (ref "C1") (pin "1") (pinfunction "1_1") (pintype "passive"))
      (node (ref "C2") (pin "1") (pinfunction "1_1") (pintype "passive"))
      (node (ref "D1") (pin "1") (pinfunction "K_1") (pintype "passive"))
      (node (ref "L1") (pin "1") (pinfunction "1_1") (pintype "passive"))
    )
    (net (code "25") (name "Net-(D2-A)") (class "Default")
      (node (ref "D2") (pin "1") (pinfunction "A_1") (pintype "passive"))
      (node (ref "T1") (pin "12") (pinfunction "12_12") (pintype "passive"))
    )
    (net (code "26") (name "Net-(D3-K)") (class "Default")
      (node (ref "D3") (pin "2") (pinfunction "K_2") (pintype "passive"))
      (node (ref "D4") (pin "2") (pinfunction "K_2") (pintype "passive"))
    )
    (net (code "27") (name "Net-(D4-A)") (class "Default")
      (node (ref "D4") (pin "1") (pinfunction "A_1") (pintype "passive"))
      (node (ref "D6") (pin "1") (pinfunction "A_1") (pintype "passive"))
      (node (ref "Q1") (pin "2") (pinfunction "D_2") (pintype "passive"))
      (node (ref "T1") (pin "2") (pinfunction "1_2") (pintype "passive"))
    )
    (net (code "28") (name "Net-(D5-A)") (class "Default")
      (node (ref "D5") (pin "1") (pinfunction "A_1") (pintype "passive"))
      (node (ref "T1") (pin "9") (pinfunction "9_9") (pintype "passive"))
    )
    (net (code "29") (name "Net-(D6-K)") (class "Default")
      (node (ref "D6") (pin "2") (pinfunction "K_2") (pintype "passive"))
      (node (ref "R3") (pin "1") (pinfunction "1_1") (pintype "passive"))
    )
    (net (code "30") (name "Net-(D7-A)") (class "Default")
      (node (ref "D7") (pin "1") (pinfunction "A_1") (pintype "passive"))
      (node (ref "T1") (pin "6") (pinfunction "6_6") (pintype "passive"))
    )
    (net (code "31") (name "Net-(D8-A)") (class "Default")
      (node (ref "D8") (pin "1") (pinfunction "A_1") (pintype "passive"))
      (node (ref "D9") (pin "1") (pinfunction "A_1") (pintype "passive"))
      (node (ref "R12") (pin "1") (pinfunction "1_1") (pintype "passive"))
    )
    (net (code "32") (name "Net-(D10-K)") (class "Default")
      (node (ref "D10") (pin "2") (pinfunction "K_2") (pintype "passive"))
      (node (ref "D11") (pin "2") (pinfunction "K_2") (pintype "passive"))
      (node (ref "T1") (pin "10") (pinfunction "10_10") (pintype "passive"))
    )
    (net (code "33") (name "Net-(D12-K)") (class "Default")
      (node (ref "D12") (pin "2") (pinfunction "K_2") (pintype "passive"))
      (node (ref "D13") (pin "2") (pinfunction "K_2") (pintype "passive"))
      (node (ref "T1") (pin "7") (pinfunction "7_7") (pintype "passive"))
    )
    (net (code "34") (name "Net-(Q1-G)") (class "Default")
      (node (ref "Q1") (pin "1") (pinfunction "G_1") (pintype "passive"))
      (node (ref "R5") (pin "2") (pinfunction "2_2") (pintype "passive"))
      (node (ref "R8") (pin "2") (pinfunction "2_2") (pintype "passive"))
    )
    (net (code "35") (name "Net-(Q1-S)") (class "Default")
      (node (ref "Q1") (pin "3") (pinfunction "S_3") (pintype "passive"))
      (node (ref "R11") (pin "2") (pinfunction "2_2") (pintype "passive"))
      (node (ref "R8") (pin "1") (pinfunction "1_1") (pintype "passive"))
      (node (ref "R9") (pin "2") (pinfunction "2_2") (pintype "passive"))
    )
    (net (code "36") (name "Net-(U2-A)") (class "Default")
      (node (ref "R14") (pin "1") (pinfunction "1_1") (pintype "passive"))
      (node (ref "R17") (pin "2") (pinfunction "2_2") (pintype "passive"))
      (node (ref "U2") (pin "1") (pinfunction "A_1") (pintype "passive"))
    )
    (net (code "37") (name "Net-(U2-C)") (class "Default")
      (node (ref "C18") (pin "2") (pinfunction "2_2") (pintype "passive"))
      (node (ref "R13") (pin "1") (pinfunction "1_1") (pintype "passive"))
      (node (ref "R16") (pin "1") (pinfunction "1_1") (pintype "passive"))
      (node (ref "U2") (pin "4") (pinfunction "C_4") (pintype "passive"))
    )
    (net (code "38") (name "Net-(U2-E)") (class "Default")
      (node (ref "C19") (pin "1") (pinfunction "1_1") (pintype "passive"))
      (node (ref "R18") (pin "2") (pinfunction "2_2") (pintype "passive"))
      (node (ref "U2") (pin "3") (pinfunction "E_3") (pintype "passive"))
    )
    (net (code "39") (name "Net-(U2-K)") (class "Default")
      (node (ref "C20") (pin "1") (pinfunction "1_1") (pintype "passive"))
      (node (ref "R17") (pin "1") (pinfunction "1_1") (pintype "passive"))
      (node (ref "R20") (pin "2") (pinfunction "2_2") (pintype "passive"))
      (node (ref "U2") (pin "2") (pinfunction "K_2") (pintype "passive"))
      (node (ref "U3") (pin "1") (pinfunction "CATHODE_1") (pintype "passive"))
    )
    (net (code "40") (name "Net-(U3-REF)") (class "Default")
      (node (ref "C20") (pin "2") (pinfunction "2_2") (pintype "passive"))
      (node (ref "R15") (pin "2") (pinfunction "2_2") (pintype "passive"))
      (node (ref "R20") (pin "1") (pinfunction "1_1") (pintype "passive"))
      (node (ref "R21") (pin "2") (pinfunction "2_2") (pintype "passive"))
      (node (ref "U3") (pin "2") (pinfunction "REF_2") (pintype "input"))
    )
    (net (code "41") (name "Net-(U4-BOOT)") (class "Default")
      (node (ref "R22") (pin "2") (pinfunction "2_2") (pintype "passive"))
      (node (ref "U4") (pin "6") (pinfunction "BOOT_6") (pintype "power_in"))
    )
    (net (code "42") (name "Net-(U4-EN)") (class "Default")
      (node (ref "R24") (pin "1") (pinfunction "1_1") (pintype "passive"))
      (node (ref "R28") (pin "2") (pinfunction "2_2") (pintype "passive"))
      (node (ref "U4") (pin "5") (pinfunction "EN_5") (pintype "input"))
    )
    (net (code "43") (name "Net-(U4-FB)") (class "Default")
      (node (ref "C36") (pin "1") (pinfunction "1_1") (pintype "passive"))
      (node (ref "R26") (pin "1") (pinfunction "1_1") (pintype "passive"))
      (node (ref "R30") (pin "2") (pinfunction "2_2") (pintype "passive"))
      (node (ref "U4") (pin "4") (pinfunction "FB_4") (pintype "input"))
    )
    (net (code "44") (name "Net-(U4-SW)") (class "Default")
      (node (ref "C21") (pin "2") (pinfunction "2_2") (pintype "passive"))
      (node (ref "L2") (pin "1") (pinfunction "1_1") (pintype "passive"))
      (node (ref "U4") (pin "2") (pinfunction "SW_2") (pintype "power_in"))
    )
    (net (code "45") (name "Net-(U5-BOOT)") (class "Default")
      (node (ref "R23") (pin "2") (pinfunction "2_2") (pintype "passive"))
      (node (ref "U5") (pin "6") (pinfunction "BOOT_6") (pintype "power_in"))
    )
    (net (code "46") (name "Net-(U5-EN)") (class "Default")
      (node (ref "R25") (pin "1") (pinfunction "1_1") (pintype "passive"))
      (node (ref "R29") (pin "2") (pinfunction "2_2") (pintype "passive"))
      (node (ref "U5") (pin "5") (pinfunction "EN_5") (pintype "input"))
    )
    (net (code "47") (name "Net-(U5-FB)") (class "Default")
      (node (ref "C35") (pin "1") (pinfunction "1_1") (pintype "passive"))
      (node (ref "R27") (pin "1") (pinfunction "1_1") (pintype "passive"))
      (node (ref "R31") (pin "2") (pinfunction "2_2") (pintype "passive"))
      (node (ref "U5") (pin "4") (pinfunction "FB_4") (pintype "input"))
    )
    (net (code "48") (name "Net-(U5-SW)") (class "Default")
      (node (ref "C22") (pin "2") (pinfunction "2_2") (pintype "passive"))
      (node (ref "L3") (pin "1") (pinfunction "1_1") (pintype "passive"))
      (node (ref "U5") (pin "2") (pinfunction "SW_2") (pintype "power_in"))
    )
    (net (code "49") (name "VCC_AUX") (class "Default")
      (node (ref "C15") (pin "1") (pinfunction "1_1") (pintype "passive"))
      (node (ref "C16") (pin "2") (pinfunction "2_2") (pintype "passive"))
      (node (ref "C17") (pin "1") (pinfunction "1_1") (pintype "passive"))
      (node (ref "D8") (pin "2") (pinfunction "K_2") (pintype "passive"))
      (node (ref "D9") (pin "2") (pinfunction "K_2") (pintype "passive"))
      (node (ref "R16") (pin "2") (pinfunction "2_2") (pintype "passive"))
      (node (ref "U1") (pin "1") (pinfunction "VDD_1") (pintype "power_in"))
    )
    (net (code "50") (name "unconnected-(P3-Pad5)") (class "Default")
      (node (ref "P3") (pin "5") (pinfunction "5_5") (pintype "passive+no_connect"))
    )
    (net (code "51") (name "unconnected-(P3-Pad6)") (class "Default")
      (node (ref "P3") (pin "6") (pinfunction "6_6") (pintype "passive+no_connect"))
    )
    (net (code "52") (name "unconnected-(P3-Pad7)") (class "Default")
      (node (ref "P3") (pin "7") (pinfunction "7_7") (pintype "passive+no_connect"))
    )
    (net (code "53") (name "unconnected-(P3-Pad8)") (class "Default")
      (node (ref "P3") (pin "8") (pinfunction "8_8") (pintype "passive+no_connect"))
    )
    (net (code "54") (name "unconnected-(T1-Pad3)") (class "Default")
      (node (ref "T1") (pin "3") (pintype "passive"))
    )
    (net (code "55") (name "unconnected-(T1-Pad8)") (class "Default")
      (node (ref "T1") (pin "8") (pintype "passive"))
    )
    (net (code "56") (name "unconnected-(U1-NC-Pad7)") (class "Default")
      (node (ref "U1") (pin "7") (pinfunction "NC_7") (pintype "passive"))
    )
  )
)
